# zeta2rework_lw_v22_wo_transistor.net
KiCad netlist of a schematic drawn in EAGLE
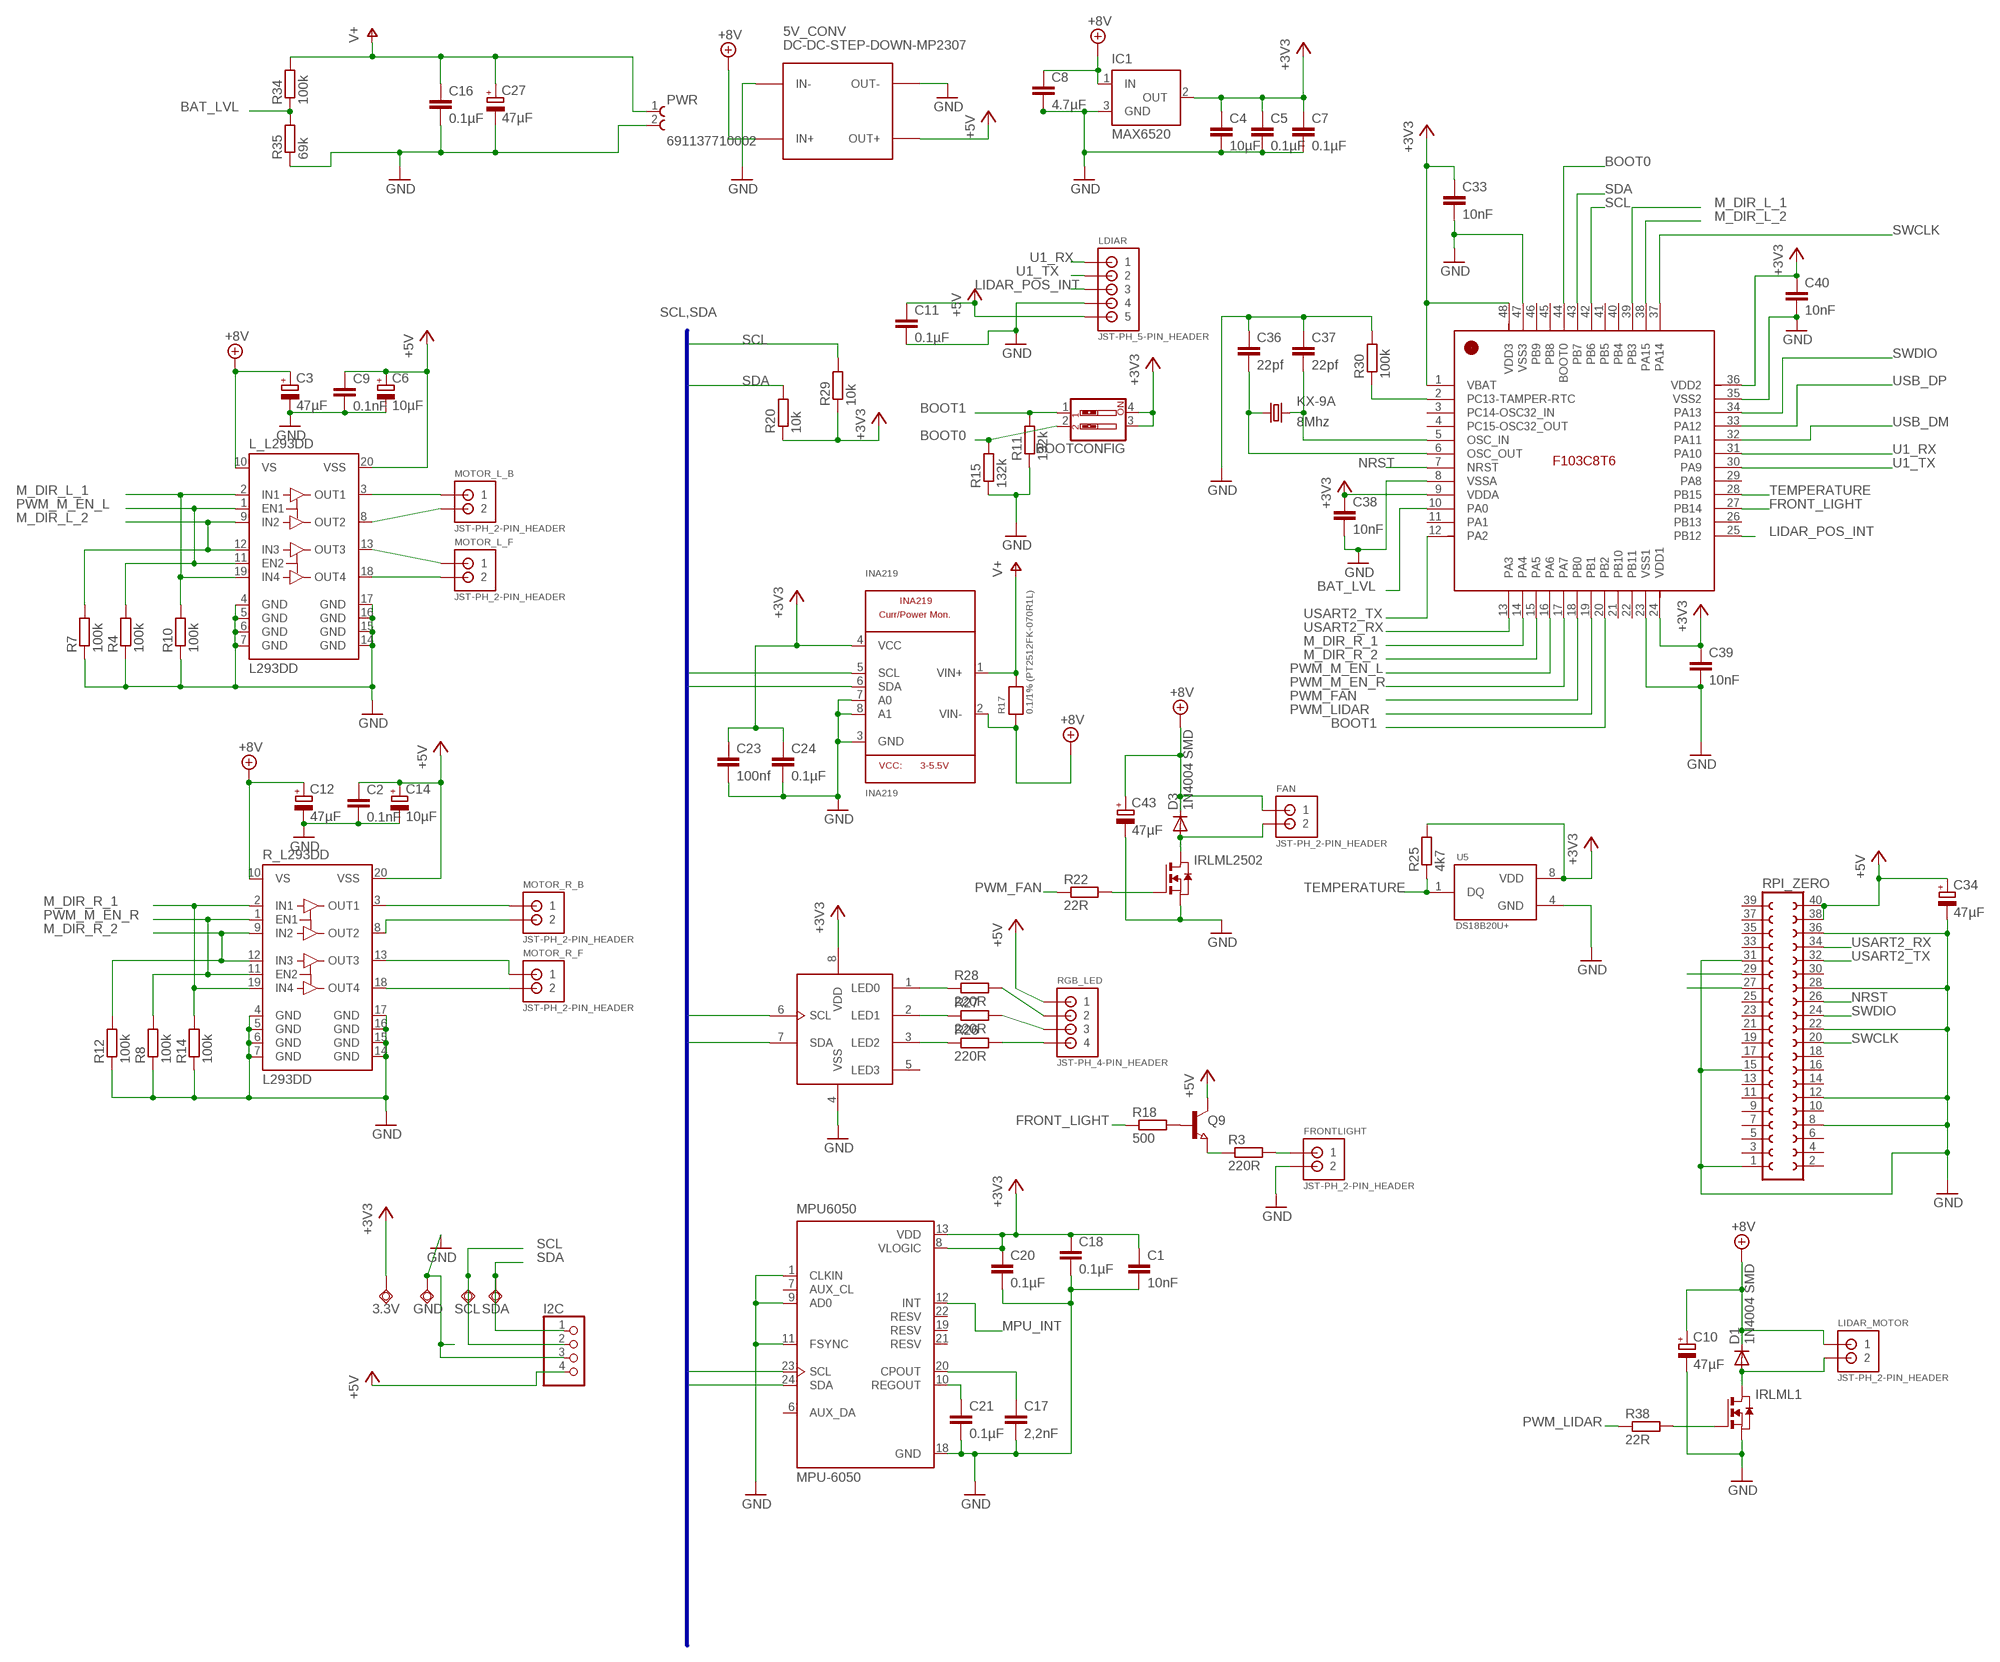
[diagram p0: schematic, sheet 1]

(export (version "E")
  (design (tool "Eeschema 10.0.6"))
  (components
    (comp (ref "3.3V")
      (value "TPSQTP20R")
      (footprint "eagle-import:TP20R")
      (libsource (lib "eagle-import") (part "TPSQTP20R"))
    )
    (comp (ref "5V_CONV")
      (value "DC-DC-STEP-DOWN-MP2307")
      (footprint "eagle-import:DC-DC-STEP-DOWN-MP2307")
      (libsource (lib "eagle-import") (part "DC-DC-STEP-DOWN-MP2307"))
    )
    (comp (ref "BOOTCONFIG")
      (value "SW_DIP-2")
      (footprint "eagle-import:EDG-02")
      (libsource (lib "eagle-import") (part "SW_DIP-2"))
    )
    (comp (ref "C1")
      (value "10nF")
      (footprint "eagle-import:C1206")
      (libsource (lib "eagle-import") (part "C-EUC1206"))
    )
    (comp (ref "C2")
      (value "0.1nF")
      (footprint "eagle-import:C1206")
      (libsource (lib "eagle-import") (part "C-EUC1206"))
    )
    (comp (ref "C3")
      (value "47µF")
      (footprint "eagle-import:UD-4X5,8_NICHICON")
      (libsource (lib "eagle-import") (part "CPOL-EUUD-4X5,8"))
    )
    (comp (ref "C4")
      (value "10µF")
      (footprint "eagle-import:C1206")
      (libsource (lib "eagle-import") (part "C-EUC1206"))
    )
    (comp (ref "C5")
      (value "0.1µF")
      (footprint "eagle-import:C1206")
      (libsource (lib "eagle-import") (part "C-EUC1206"))
    )
    (comp (ref "C6")
      (value "10µF")
      (footprint "eagle-import:UD-4X5,8_NICHICON")
      (libsource (lib "eagle-import") (part "CPOL-EUUD-4X5,8"))
    )
    (comp (ref "C7")
      (value "0.1µF")
      (footprint "eagle-import:C1206")
      (libsource (lib "eagle-import") (part "C-EUC1206"))
    )
    (comp (ref "C8")
      (value "4.7µF")
      (footprint "eagle-import:C1206")
      (libsource (lib "eagle-import") (part "C-EUC1206"))
    )
    (comp (ref "C9")
      (value "0.1nF")
      (footprint "eagle-import:C1206")
      (libsource (lib "eagle-import") (part "C-EUC1206"))
    )
    (comp (ref "C10")
      (value "47µF")
      (footprint "eagle-import:UD-4X5,8_NICHICON")
      (libsource (lib "eagle-import") (part "CPOL-EUUD-4X5,8"))
    )
    (comp (ref "C11")
      (value "0.1µF")
      (footprint "eagle-import:C1206")
      (libsource (lib "eagle-import") (part "C-EUC1206"))
    )
    (comp (ref "C12")
      (value "47µF")
      (footprint "eagle-import:UD-4X5,8_NICHICON")
      (libsource (lib "eagle-import") (part "CPOL-EUUD-4X5,8"))
    )
    (comp (ref "C14")
      (value "10µF")
      (footprint "eagle-import:UD-4X5,8_NICHICON")
      (libsource (lib "eagle-import") (part "CPOL-EUUD-4X5,8"))
    )
    (comp (ref "C16")
      (value "0.1µF")
      (footprint "eagle-import:C1206")
      (libsource (lib "eagle-import") (part "C-EUC1206"))
    )
    (comp (ref "C17")
      (value "2,2nF")
      (footprint "eagle-import:C1206")
      (libsource (lib "eagle-import") (part "C-EUC1206"))
    )
    (comp (ref "C18")
      (value "0.1µF")
      (footprint "eagle-import:C1206")
      (libsource (lib "eagle-import") (part "C-EUC1206"))
    )
    (comp (ref "C20")
      (value "0.1µF")
      (footprint "eagle-import:C1206")
      (libsource (lib "eagle-import") (part "C-EUC1206"))
    )
    (comp (ref "C21")
      (value "0.1µF")
      (footprint "eagle-import:C1206")
      (libsource (lib "eagle-import") (part "C-EUC1206"))
    )
    (comp (ref "C23")
      (value "100nf")
      (footprint "eagle-import:C1206")
      (libsource (lib "eagle-import") (part "C-EUC1206"))
    )
    (comp (ref "C24")
      (value "0.1µF")
      (footprint "eagle-import:C1206")
      (libsource (lib "eagle-import") (part "C-EUC1206"))
    )
    (comp (ref "C27")
      (value "47µF")
      (footprint "eagle-import:UD-4X5,8_NICHICON")
      (libsource (lib "eagle-import") (part "CPOL-EUUD-4X5,8"))
    )
    (comp (ref "C33")
      (value "10nF")
      (footprint "eagle-import:C1206")
      (libsource (lib "eagle-import") (part "C-EUC1206"))
    )
    (comp (ref "C34")
      (value "47µF")
      (footprint "eagle-import:UD-4X5,8_NICHICON")
      (libsource (lib "eagle-import") (part "CPOL-EUUD-4X5,8"))
    )
    (comp (ref "C36")
      (value "22pf")
      (footprint "eagle-import:C1206")
      (libsource (lib "eagle-import") (part "C-EUC1206"))
    )
    (comp (ref "C37")
      (value "22pf")
      (footprint "eagle-import:C1206")
      (libsource (lib "eagle-import") (part "C-EUC1206"))
    )
    (comp (ref "C38")
      (value "10nF")
      (footprint "eagle-import:C1206")
      (libsource (lib "eagle-import") (part "C-EUC1206"))
    )
    (comp (ref "C39")
      (value "10nF")
      (footprint "eagle-import:C1206")
      (libsource (lib "eagle-import") (part "C-EUC1206"))
    )
    (comp (ref "C40")
      (value "10nF")
      (footprint "eagle-import:C1206")
      (libsource (lib "eagle-import") (part "C-EUC1206"))
    )
    (comp (ref "C43")
      (value "47µF")
      (footprint "eagle-import:UD-4X5,8_NICHICON")
      (libsource (lib "eagle-import") (part "CPOL-EUUD-4X5,8"))
    )
    (comp (ref "D1")
      (value "1N4004 SMD")
      (footprint "eagle-import:DO214AC")
      (libsource (lib "eagle-import") (part "DIODE-DO214AC"))
    )
    (comp (ref "D3")
      (value "1N4004 SMD")
      (footprint "eagle-import:DO214AC")
      (libsource (lib "eagle-import") (part "DIODE-DO214AC"))
    )
    (comp (ref "FAN")
      (value "JST-PH_2-PIN_HEADER")
      (footprint "eagle-import:JST_B2B-PH_HEADER")
      (libsource (lib "eagle-import") (part "JST-PH_2-PIN_HEADER"))
    )
    (comp (ref "FRONTLIGHT")
      (value "JST-PH_2-PIN_HEADER")
      (footprint "eagle-import:JST_B2B-PH_HEADER")
      (libsource (lib "eagle-import") (part "JST-PH_2-PIN_HEADER"))
    )
    (comp (ref "GND")
      (value "TPSQTP20R")
      (footprint "eagle-import:TP20R")
      (libsource (lib "eagle-import") (part "TPSQTP20R"))
    )
    (comp (ref "I2C")
      (value "PINHD-1X4")
      (footprint "eagle-import:1X04")
      (libsource (lib "eagle-import") (part "PINHD-1X4"))
    )
    (comp (ref "IC1")
      (value "MAX6520")
      (footprint "eagle-import:SOT23")
      (fields (field (name "MF") "MAXIM") (field (name "MPN") "MAX6520EUR-T"))
      (libsource (lib "eagle-import") (part "MAX6520"))
    )
    (comp (ref "INA219")
      (value "INA219")
      (footprint "eagle-import:SOT23-8")
      (fields (field (name "MF") "Texas Instruments"))
      (libsource (lib "eagle-import") (part "INA219"))
    )
    (comp (ref "IRLML1")
      (value "NMOSSOT23")
      (footprint "eagle-import:SOT-23")
      (libsource (lib "eagle-import") (part "NMOSSOT23"))
    )
    (comp (ref "IRLML2502")
      (value "NMOSSOT23")
      (footprint "eagle-import:SOT-23")
      (libsource (lib "eagle-import") (part "NMOSSOT23"))
    )
    (comp (ref "KX-9A")
      (value "8Mhz")
      (footprint "eagle-import:5.0X3.2_KX-9A")
      (libsource (lib "eagle-import") (part "KX-9A"))
    )
    (comp (ref "LDIAR")
      (value "JST-PH_5-PIN_HEADER")
      (footprint "eagle-import:JST_B5B-PH_HEADER")
      (libsource (lib "eagle-import") (part "JST-PH_5-PIN_HEADER"))
    )
    (comp (ref "LIDAR_MOTOR")
      (value "JST-PH_2-PIN_HEADER")
      (footprint "eagle-import:JST_B2B-PH_HEADER")
      (libsource (lib "eagle-import") (part "JST-PH_2-PIN_HEADER"))
    )
    (comp (ref "L_L293DD")
      (value "L293DD")
      (footprint "eagle-import:SO20")
      (libsource (lib "eagle-import") (part "L293DD"))
    )
    (comp (ref "MOTOR_L_B")
      (value "JST-PH_2-PIN_HEADER")
      (footprint "eagle-import:JST_B2B-PH_HEADER")
      (libsource (lib "eagle-import") (part "JST-PH_2-PIN_HEADER"))
    )
    (comp (ref "MOTOR_L_F")
      (value "JST-PH_2-PIN_HEADER")
      (footprint "eagle-import:JST_B2B-PH_HEADER")
      (libsource (lib "eagle-import") (part "JST-PH_2-PIN_HEADER"))
    )
    (comp (ref "MOTOR_R_B")
      (value "JST-PH_2-PIN_HEADER")
      (footprint "eagle-import:JST_B2B-PH_HEADER")
      (libsource (lib "eagle-import") (part "JST-PH_2-PIN_HEADER"))
    )
    (comp (ref "MOTOR_R_F")
      (value "JST-PH_2-PIN_HEADER")
      (footprint "eagle-import:JST_B2B-PH_HEADER")
      (libsource (lib "eagle-import") (part "JST-PH_2-PIN_HEADER"))
    )
    (comp (ref "MPU6050")
      (value "MPU-6050")
      (footprint "eagle-import:QFN50P400X400X95-24N")
      (fields (field (name "MF") "TDK"))
      (libsource (lib "eagle-import") (part "MPU-6050"))
    )
    (comp (ref "PCA9533")
      (value "PCA9533")
      (footprint "eagle-import:SOIC8")
      (libsource (lib "eagle-import") (part "PCA9533"))
    )
    (comp (ref "PWR")
      (value "691137710002")
      (footprint "eagle-import:691137710002")
      (fields (field (name "MF") "Wurth Electronics"))
      (libsource (lib "eagle-import") (part "691137710002"))
    )
    (comp (ref "Q9")
      (value "NPN-TRANSISTOR_SOT23")
      (footprint "eagle-import:SOT23")
      (libsource (lib "eagle-import") (part "NPN-TRANSISTOR_SOT23"))
    )
    (comp (ref "R3")
      (value "220R")
      (footprint "eagle-import:R0603")
      (libsource (lib "eagle-import") (part "R-EU_R0603"))
    )
    (comp (ref "R4")
      (value "100k")
      (footprint "eagle-import:R0603")
      (libsource (lib "eagle-import") (part "R-EU_R0603"))
    )
    (comp (ref "R7")
      (value "100k")
      (footprint "eagle-import:R0603")
      (libsource (lib "eagle-import") (part "R-EU_R0603"))
    )
    (comp (ref "R8")
      (value "100k")
      (footprint "eagle-import:R0603")
      (libsource (lib "eagle-import") (part "R-EU_R0603"))
    )
    (comp (ref "R10")
      (value "100k")
      (footprint "eagle-import:R0603")
      (libsource (lib "eagle-import") (part "R-EU_R0603"))
    )
    (comp (ref "R11")
      (value "132k")
      (footprint "eagle-import:R0603")
      (libsource (lib "eagle-import") (part "R-EU_R0603"))
    )
    (comp (ref "R12")
      (value "100k")
      (footprint "eagle-import:R0603")
      (libsource (lib "eagle-import") (part "R-EU_R0603"))
    )
    (comp (ref "R14")
      (value "100k")
      (footprint "eagle-import:R0603")
      (libsource (lib "eagle-import") (part "R-EU_R0603"))
    )
    (comp (ref "R15")
      (value "132k")
      (footprint "eagle-import:R0603")
      (libsource (lib "eagle-import") (part "R-EU_R0603"))
    )
    (comp (ref "R17")
      (value "0.1/1% (PT2512FK-070R1L)")
      (footprint "eagle-import:2512")
      (libsource (lib "eagle-import") (part "RESISTOR2512"))
    )
    (comp (ref "R18")
      (value "500")
      (footprint "eagle-import:R0603")
      (libsource (lib "eagle-import") (part "R-EU_R0603"))
    )
    (comp (ref "R20")
      (value "10k")
      (footprint "eagle-import:R0603")
      (libsource (lib "eagle-import") (part "R-EU_R0603"))
    )
    (comp (ref "R22")
      (value "22R")
      (footprint "eagle-import:R0603")
      (libsource (lib "eagle-import") (part "R-EU_R0603"))
    )
    (comp (ref "R25")
      (value "4k7")
      (footprint "eagle-import:R0603")
      (libsource (lib "eagle-import") (part "R-EU_R0603"))
    )
    (comp (ref "R26")
      (value "220R")
      (footprint "eagle-import:R0603")
      (libsource (lib "eagle-import") (part "R-EU_R0603"))
    )
    (comp (ref "R27")
      (value "220R")
      (footprint "eagle-import:R0603")
      (libsource (lib "eagle-import") (part "R-EU_R0603"))
    )
    (comp (ref "R28")
      (value "220R")
      (footprint "eagle-import:R0603")
      (libsource (lib "eagle-import") (part "R-EU_R0603"))
    )
    (comp (ref "R29")
      (value "10k")
      (footprint "eagle-import:R0603")
      (libsource (lib "eagle-import") (part "R-EU_R0603"))
    )
    (comp (ref "R30")
      (value "100k")
      (footprint "eagle-import:R0603")
      (libsource (lib "eagle-import") (part "R-EU_R0603"))
    )
    (comp (ref "R34")
      (value "100k")
      (footprint "eagle-import:R0603")
      (libsource (lib "eagle-import") (part "R-EU_R0603"))
    )
    (comp (ref "R35")
      (value "69k")
      (footprint "eagle-import:R0603")
      (libsource (lib "eagle-import") (part "R-EU_R0603"))
    )
    (comp (ref "R38")
      (value "22R")
      (footprint "eagle-import:R0603")
      (libsource (lib "eagle-import") (part "R-EU_R0603"))
    )
    (comp (ref "RGB_LED")
      (value "JST-PH_4-PIN_HEADER")
      (footprint "eagle-import:JST_B4B-PH_HEADER")
      (libsource (lib "eagle-import") (part "JST-PH_4-PIN_HEADER"))
    )
    (comp (ref "RPI_ZERO")
      (value "FE20-2")
      (footprint "eagle-import:FE20-2")
      (libsource (lib "eagle-import") (part "FE20-2"))
    )
    (comp (ref "R_L293DD")
      (value "L293DD")
      (footprint "eagle-import:SO20")
      (libsource (lib "eagle-import") (part "L293DD"))
    )
    (comp (ref "SCL")
      (value "TPSQTP20R")
      (footprint "eagle-import:TP20R")
      (libsource (lib "eagle-import") (part "TPSQTP20R"))
    )
    (comp (ref "SDA")
      (value "TPSQTP20R")
      (footprint "eagle-import:TP20R")
      (libsource (lib "eagle-import") (part "TPSQTP20R"))
    )
    (comp (ref "STM32F103CB")
      (value "STM32F103CB")
      (footprint "eagle-import:LQFP48_7X7MM_0.5MMPP")
      (fields (field (name "MF") "STMicroelectronics") (field (name "MP") "STM32F103C8T6"))
      (libsource (lib "eagle-import") (part "STM32F103C8T6"))
    )
    (comp (ref "U5")
      (value "DS18B20U+")
      (footprint "eagle-import:SOP65P490X95-8N")
      (fields (field (name "MF") "Maxim"))
      (libsource (lib "eagle-import") (part "DS18B20U+"))
    )
  )
  (nets
    (net (code "1") (name "+3V3") (class "Default")
      (node (ref "3.3V") (pin "TP") (pinfunction "TP_TP") (pintype "input"))
      (node (ref "BOOTCONFIG") (pin "3") (pinfunction "3_3") (pintype "passive"))
      (node (ref "BOOTCONFIG") (pin "4") (pinfunction "4_4") (pintype "passive"))
      (node (ref "C1") (pin "1") (pinfunction "1_1") (pintype "passive"))
      (node (ref "C18") (pin "1") (pinfunction "1_1") (pintype "passive"))
      (node (ref "C20") (pin "1") (pinfunction "1_1") (pintype "passive"))
      (node (ref "C23") (pin "1") (pinfunction "1_1") (pintype "passive"))
      (node (ref "C24") (pin "1") (pinfunction "1_1") (pintype "passive"))
      (node (ref "C33") (pin "1") (pinfunction "1_1") (pintype "passive"))
      (node (ref "C38") (pin "1") (pinfunction "1_1") (pintype "passive"))
      (node (ref "C39") (pin "1") (pinfunction "1_1") (pintype "passive"))
      (node (ref "C4") (pin "1") (pinfunction "1_1") (pintype "passive"))
      (node (ref "C40") (pin "1") (pinfunction "1_1") (pintype "passive"))
      (node (ref "C5") (pin "1") (pinfunction "1_1") (pintype "passive"))
      (node (ref "C7") (pin "1") (pinfunction "1_1") (pintype "passive"))
      (node (ref "IC1") (pin "2") (pinfunction "OUT_2") (pintype "output"))
      (node (ref "INA219") (pin "4") (pinfunction "VCC_4") (pintype "bidirectional"))
      (node (ref "MPU6050") (pin "13") (pinfunction "VDD_13") (pintype "power_in"))
      (node (ref "MPU6050") (pin "8") (pinfunction "VLOGIC_8") (pintype "power_in"))
      (node (ref "PCA9533") (pin "8") (pinfunction "VDD_8") (pintype "power_in"))
      (node (ref "R20") (pin "1") (pinfunction "1_1") (pintype "passive"))
      (node (ref "R25") (pin "2") (pinfunction "2_2") (pintype "passive"))
      (node (ref "R29") (pin "1") (pinfunction "1_1") (pintype "passive"))
      (node (ref "STM32F103CB") (pin "1") (pinfunction "VBAT_1") (pintype "bidirectional"))
      (node (ref "STM32F103CB") (pin "24") (pinfunction "VDD1_24") (pintype "bidirectional"))
      (node (ref "STM32F103CB") (pin "36") (pinfunction "VDD2_36") (pintype "bidirectional"))
      (node (ref "STM32F103CB") (pin "48") (pinfunction "VDD3_48") (pintype "bidirectional"))
      (node (ref "STM32F103CB") (pin "9") (pinfunction "VDDA_9") (pintype "bidirectional"))
      (node (ref "U5") (pin "8") (pinfunction "VDD_8") (pintype "power_in"))
    )
    (net (code "2") (name "+5V") (class "Default")
      (node (ref "5V_CONV") (pin "OUT+") (pinfunction "OUT+_OUT+") (pintype "bidirectional"))
      (node (ref "C11") (pin "1") (pinfunction "1_1") (pintype "passive"))
      (node (ref "C14") (pin "+") (pinfunction "+_+") (pintype "passive"))
      (node (ref "C2") (pin "1") (pinfunction "1_1") (pintype "passive"))
      (node (ref "C34") (pin "+") (pinfunction "+_+") (pintype "passive"))
      (node (ref "C6") (pin "+") (pinfunction "+_+") (pintype "passive"))
      (node (ref "C9") (pin "1") (pinfunction "1_1") (pintype "passive"))
      (node (ref "I2C") (pin "4") (pinfunction "4_4") (pintype "passive"))
      (node (ref "LDIAR") (pin "P5") (pinfunction "5_P5") (pintype "bidirectional"))
      (node (ref "L_L293DD") (pin "20") (pinfunction "VSS_20") (pintype "power_in"))
      (node (ref "Q9") (pin "3") (pinfunction "C_3") (pintype "passive"))
      (node (ref "RGB_LED") (pin "P1") (pinfunction "1_P1") (pintype "bidirectional"))
      (node (ref "RPI_ZERO") (pin "38") (pinfunction "38_38") (pintype "passive"))
      (node (ref "RPI_ZERO") (pin "40") (pinfunction "40_40") (pintype "passive"))
      (node (ref "R_L293DD") (pin "20") (pinfunction "VSS_20") (pintype "power_in"))
    )
    (net (code "3") (name "+8V") (class "Default")
      (node (ref "5V_CONV") (pin "IN+") (pinfunction "IN+_IN+") (pintype "bidirectional"))
      (node (ref "C10") (pin "+") (pinfunction "+_+") (pintype "passive"))
      (node (ref "C12") (pin "+") (pinfunction "+_+") (pintype "passive"))
      (node (ref "C3") (pin "+") (pinfunction "+_+") (pintype "passive"))
      (node (ref "C43") (pin "+") (pinfunction "+_+") (pintype "passive"))
      (node (ref "C8") (pin "1") (pinfunction "1_1") (pintype "passive"))
      (node (ref "D1") (pin "C") (pinfunction "C_C") (pintype "passive"))
      (node (ref "D3") (pin "C") (pinfunction "C_C") (pintype "passive"))
      (node (ref "FAN") (pin "P1") (pinfunction "1_P1") (pintype "bidirectional"))
      (node (ref "IC1") (pin "1") (pinfunction "IN_1") (pintype "input"))
      (node (ref "INA219") (pin "2") (pinfunction "VIN-_2") (pintype "bidirectional"))
      (node (ref "LIDAR_MOTOR") (pin "P1") (pinfunction "1_P1") (pintype "bidirectional"))
      (node (ref "L_L293DD") (pin "10") (pinfunction "VS_10") (pintype "power_in"))
      (node (ref "R17") (pin "1") (pinfunction "1_1") (pintype "passive"))
      (node (ref "R_L293DD") (pin "10") (pinfunction "VS_10") (pintype "power_in"))
    )
    (net (code "4") (name "/BAT_LVL") (class "Default")
      (node (ref "R34") (pin "1") (pinfunction "1_1") (pintype "passive"))
      (node (ref "R35") (pin "2") (pinfunction "2_2") (pintype "passive"))
      (node (ref "STM32F103CB") (pin "10") (pinfunction "PA0_10") (pintype "bidirectional"))
    )
    (net (code "5") (name "/BOOT0") (class "Default")
      (node (ref "BOOTCONFIG") (pin "2") (pinfunction "2_2") (pintype "passive"))
      (node (ref "R15") (pin "2") (pinfunction "2_2") (pintype "passive"))
      (node (ref "STM32F103CB") (pin "44") (pinfunction "BOOT0_44") (pintype "bidirectional"))
    )
    (net (code "6") (name "/BOOT1") (class "Default")
      (node (ref "BOOTCONFIG") (pin "1") (pinfunction "1_1") (pintype "passive"))
      (node (ref "R11") (pin "2") (pinfunction "2_2") (pintype "passive"))
      (node (ref "STM32F103CB") (pin "20") (pinfunction "PB2_20") (pintype "bidirectional"))
    )
    (net (code "7") (name "/FRONT_LIGHT") (class "Default")
      (node (ref "R18") (pin "1") (pinfunction "1_1") (pintype "passive"))
      (node (ref "STM32F103CB") (pin "27") (pinfunction "PB14_27") (pintype "bidirectional"))
    )
    (net (code "8") (name "/LIDAR_POS_INT") (class "Default")
      (node (ref "LDIAR") (pin "P3") (pinfunction "3_P3") (pintype "bidirectional"))
      (node (ref "STM32F103CB") (pin "25") (pinfunction "PB12_25") (pintype "bidirectional"))
    )
    (net (code "9") (name "/MPU_INT") (class "Default")
      (node (ref "MPU6050") (pin "12") (pinfunction "INT_12") (pintype "output"))
    )
    (net (code "10") (name "/M_DIR_L_1") (class "Default")
      (node (ref "L_L293DD") (pin "19") (pinfunction "IN4_19") (pintype "input"))
      (node (ref "L_L293DD") (pin "2") (pinfunction "IN1_2") (pintype "input"))
      (node (ref "R10") (pin "2") (pinfunction "2_2") (pintype "passive"))
      (node (ref "STM32F103CB") (pin "39") (pinfunction "PB3_39") (pintype "bidirectional"))
    )
    (net (code "11") (name "/M_DIR_L_2") (class "Default")
      (node (ref "L_L293DD") (pin "12") (pinfunction "IN3_12") (pintype "input"))
      (node (ref "L_L293DD") (pin "9") (pinfunction "IN2_9") (pintype "input"))
      (node (ref "R7") (pin "2") (pinfunction "2_2") (pintype "passive"))
      (node (ref "STM32F103CB") (pin "38") (pinfunction "PA15_38") (pintype "bidirectional"))
    )
    (net (code "12") (name "/M_DIR_R_1") (class "Default")
      (node (ref "R14") (pin "2") (pinfunction "2_2") (pintype "passive"))
      (node (ref "R_L293DD") (pin "19") (pinfunction "IN4_19") (pintype "input"))
      (node (ref "R_L293DD") (pin "2") (pinfunction "IN1_2") (pintype "input"))
      (node (ref "STM32F103CB") (pin "14") (pinfunction "PA4_14") (pintype "bidirectional"))
    )
    (net (code "13") (name "/M_DIR_R_2") (class "Default")
      (node (ref "R12") (pin "2") (pinfunction "2_2") (pintype "passive"))
      (node (ref "R_L293DD") (pin "12") (pinfunction "IN3_12") (pintype "input"))
      (node (ref "R_L293DD") (pin "9") (pinfunction "IN2_9") (pintype "input"))
      (node (ref "STM32F103CB") (pin "15") (pinfunction "PA5_15") (pintype "bidirectional"))
    )
    (net (code "14") (name "/NRST") (class "Default")
      (node (ref "RPI_ZERO") (pin "26") (pinfunction "26_26") (pintype "passive"))
      (node (ref "STM32F103CB") (pin "7") (pinfunction "NRST_7") (pintype "bidirectional"))
    )
    (net (code "15") (name "/PWM_FAN") (class "Default")
      (node (ref "R22") (pin "1") (pinfunction "1_1") (pintype "passive"))
      (node (ref "STM32F103CB") (pin "18") (pinfunction "PB0_18") (pintype "bidirectional"))
    )
    (net (code "16") (name "/PWM_LIDAR") (class "Default")
      (node (ref "R38") (pin "1") (pinfunction "1_1") (pintype "passive"))
      (node (ref "STM32F103CB") (pin "19") (pinfunction "PB1_19") (pintype "bidirectional"))
    )
    (net (code "17") (name "/PWM_M_EN_L") (class "Default")
      (node (ref "L_L293DD") (pin "1") (pinfunction "EN1_1") (pintype "input"))
      (node (ref "L_L293DD") (pin "11") (pinfunction "EN2_11") (pintype "input"))
      (node (ref "R4") (pin "2") (pinfunction "2_2") (pintype "passive"))
      (node (ref "STM32F103CB") (pin "16") (pinfunction "PA6_16") (pintype "bidirectional"))
    )
    (net (code "18") (name "/PWM_M_EN_R") (class "Default")
      (node (ref "R8") (pin "2") (pinfunction "2_2") (pintype "passive"))
      (node (ref "R_L293DD") (pin "1") (pinfunction "EN1_1") (pintype "input"))
      (node (ref "R_L293DD") (pin "11") (pinfunction "EN2_11") (pintype "input"))
      (node (ref "STM32F103CB") (pin "17") (pinfunction "PA7_17") (pintype "bidirectional"))
    )
    (net (code "19") (name "/SCL") (class "Default")
      (node (ref "I2C") (pin "2") (pinfunction "2_2") (pintype "passive"))
      (node (ref "INA219") (pin "5") (pinfunction "SCL_5") (pintype "bidirectional"))
      (node (ref "MPU6050") (pin "23") (pinfunction "SCL_23") (pintype "input"))
      (node (ref "PCA9533") (pin "6") (pinfunction "SCL_6") (pintype "input"))
      (node (ref "R29") (pin "2") (pinfunction "2_2") (pintype "passive"))
      (node (ref "SCL") (pin "TP") (pinfunction "TP_TP") (pintype "input"))
      (node (ref "STM32F103CB") (pin "42") (pinfunction "PB6_42") (pintype "bidirectional"))
    )
    (net (code "20") (name "/SDA") (class "Default")
      (node (ref "I2C") (pin "1") (pinfunction "1_1") (pintype "passive"))
      (node (ref "INA219") (pin "6") (pinfunction "SDA_6") (pintype "bidirectional"))
      (node (ref "MPU6050") (pin "24") (pinfunction "SDA_24") (pintype "bidirectional"))
      (node (ref "PCA9533") (pin "7") (pinfunction "SDA_7") (pintype "bidirectional"))
      (node (ref "R20") (pin "2") (pinfunction "2_2") (pintype "passive"))
      (node (ref "SDA") (pin "TP") (pinfunction "TP_TP") (pintype "input"))
      (node (ref "STM32F103CB") (pin "43") (pinfunction "PB7_43") (pintype "bidirectional"))
    )
    (net (code "21") (name "/SWCLK") (class "Default")
      (node (ref "RPI_ZERO") (pin "20") (pinfunction "20_20") (pintype "passive"))
      (node (ref "STM32F103CB") (pin "37") (pinfunction "PA14_37") (pintype "bidirectional"))
    )
    (net (code "22") (name "/SWDIO") (class "Default")
      (node (ref "RPI_ZERO") (pin "24") (pinfunction "24_24") (pintype "passive"))
      (node (ref "STM32F103CB") (pin "34") (pinfunction "PA13_34") (pintype "bidirectional"))
    )
    (net (code "23") (name "/TEMPERATURE") (class "Default")
      (node (ref "R25") (pin "1") (pinfunction "1_1") (pintype "passive"))
      (node (ref "STM32F103CB") (pin "28") (pinfunction "PB15_28") (pintype "bidirectional"))
      (node (ref "U5") (pin "1") (pinfunction "DQ_1") (pintype "bidirectional"))
    )
    (net (code "24") (name "/U1_RX") (class "Default")
      (node (ref "LDIAR") (pin "P1") (pinfunction "1_P1") (pintype "bidirectional"))
      (node (ref "STM32F103CB") (pin "31") (pinfunction "PA10_31") (pintype "bidirectional"))
    )
    (net (code "25") (name "/U1_TX") (class "Default")
      (node (ref "LDIAR") (pin "P2") (pinfunction "2_P2") (pintype "bidirectional"))
      (node (ref "STM32F103CB") (pin "30") (pinfunction "PA9_30") (pintype "bidirectional"))
    )
    (net (code "26") (name "/USART2_RX") (class "Default")
      (node (ref "RPI_ZERO") (pin "34") (pinfunction "34_34") (pintype "passive"))
      (node (ref "STM32F103CB") (pin "13") (pinfunction "PA3_13") (pintype "bidirectional"))
    )
    (net (code "27") (name "/USART2_TX") (class "Default")
      (node (ref "RPI_ZERO") (pin "32") (pinfunction "32_32") (pintype "passive"))
      (node (ref "STM32F103CB") (pin "12") (pinfunction "PA2_12") (pintype "bidirectional"))
    )
    (net (code "28") (name "/USB_DM") (class "Default")
      (node (ref "STM32F103CB") (pin "32") (pinfunction "PA11_32") (pintype "bidirectional"))
    )
    (net (code "29") (name "/USB_DP") (class "Default")
      (node (ref "STM32F103CB") (pin "33") (pinfunction "PA12_33") (pintype "bidirectional"))
    )
    (net (code "31") (name "GND") (class "Default")
      (node (ref "5V_CONV") (pin "IN-") (pinfunction "IN-_IN-") (pintype "bidirectional"))
      (node (ref "5V_CONV") (pin "OUT-") (pinfunction "OUT-_OUT-") (pintype "bidirectional"))
      (node (ref "C1") (pin "2") (pinfunction "2_2") (pintype "passive"))
      (node (ref "C10") (pin "-") (pinfunction "-_-") (pintype "passive"))
      (node (ref "C11") (pin "2") (pinfunction "2_2") (pintype "passive"))
      (node (ref "C12") (pin "-") (pinfunction "-_-") (pintype "passive"))
      (node (ref "C14") (pin "-") (pinfunction "-_-") (pintype "passive"))
      (node (ref "C16") (pin "2") (pinfunction "2_2") (pintype "passive"))
      (node (ref "C17") (pin "2") (pinfunction "2_2") (pintype "passive"))
      (node (ref "C18") (pin "2") (pinfunction "2_2") (pintype "passive"))
      (node (ref "C2") (pin "2") (pinfunction "2_2") (pintype "passive"))
      (node (ref "C20") (pin "2") (pinfunction "2_2") (pintype "passive"))
      (node (ref "C21") (pin "2") (pinfunction "2_2") (pintype "passive"))
      (node (ref "C23") (pin "2") (pinfunction "2_2") (pintype "passive"))
      (node (ref "C24") (pin "2") (pinfunction "2_2") (pintype "passive"))
      (node (ref "C27") (pin "-") (pinfunction "-_-") (pintype "passive"))
      (node (ref "C3") (pin "-") (pinfunction "-_-") (pintype "passive"))
      (node (ref "C33") (pin "2") (pinfunction "2_2") (pintype "passive"))
      (node (ref "C34") (pin "-") (pinfunction "-_-") (pintype "passive"))
      (node (ref "C36") (pin "1") (pinfunction "1_1") (pintype "passive"))
      (node (ref "C37") (pin "1") (pinfunction "1_1") (pintype "passive"))
      (node (ref "C38") (pin "2") (pinfunction "2_2") (pintype "passive"))
      (node (ref "C39") (pin "2") (pinfunction "2_2") (pintype "passive"))
      (node (ref "C4") (pin "2") (pinfunction "2_2") (pintype "passive"))
      (node (ref "C40") (pin "2") (pinfunction "2_2") (pintype "passive"))
      (node (ref "C43") (pin "-") (pinfunction "-_-") (pintype "passive"))
      (node (ref "C5") (pin "2") (pinfunction "2_2") (pintype "passive"))
      (node (ref "C6") (pin "-") (pinfunction "-_-") (pintype "passive"))
      (node (ref "C7") (pin "2") (pinfunction "2_2") (pintype "passive"))
      (node (ref "C8") (pin "2") (pinfunction "2_2") (pintype "passive"))
      (node (ref "C9") (pin "2") (pinfunction "2_2") (pintype "passive"))
      (node (ref "FRONTLIGHT") (pin "P2") (pinfunction "2_P2") (pintype "bidirectional"))
      (node (ref "GND") (pin "TP") (pinfunction "TP_TP") (pintype "input"))
      (node (ref "I2C") (pin "3") (pinfunction "3_3") (pintype "passive"))
      (node (ref "IC1") (pin "3") (pinfunction "GND_3") (pintype "power_in"))
      (node (ref "INA219") (pin "3") (pinfunction "GND_3") (pintype "bidirectional"))
      (node (ref "INA219") (pin "7") (pinfunction "A0_7") (pintype "bidirectional"))
      (node (ref "INA219") (pin "8") (pinfunction "A1_8") (pintype "bidirectional"))
      (node (ref "IRLML1") (pin "2") (pinfunction "S_2") (pintype "passive"))
      (node (ref "IRLML2502") (pin "2") (pinfunction "S_2") (pintype "passive"))
      (node (ref "LDIAR") (pin "P4") (pinfunction "4_P4") (pintype "bidirectional"))
      (node (ref "L_L293DD") (pin "14") (pinfunction "GND_14") (pintype "power_in"))
      (node (ref "L_L293DD") (pin "15") (pinfunction "GND_15") (pintype "power_in"))
      (node (ref "L_L293DD") (pin "16") (pinfunction "GND_16") (pintype "power_in"))
      (node (ref "L_L293DD") (pin "17") (pinfunction "GND_17") (pintype "power_in"))
      (node (ref "L_L293DD") (pin "4") (pinfunction "GND_4") (pintype "power_in"))
      (node (ref "L_L293DD") (pin "5") (pinfunction "GND_5") (pintype "power_in"))
      (node (ref "L_L293DD") (pin "6") (pinfunction "GND_6") (pintype "power_in"))
      (node (ref "L_L293DD") (pin "7") (pinfunction "GND_7") (pintype "power_in"))
      (node (ref "MPU6050") (pin "1") (pinfunction "CLKIN_1") (pintype "input"))
      (node (ref "MPU6050") (pin "11") (pinfunction "FSYNC_11") (pintype "input"))
      (node (ref "MPU6050") (pin "18") (pinfunction "GND_18") (pintype "power_in"))
      (node (ref "MPU6050") (pin "9") (pinfunction "AD0_9") (pintype "input"))
      (node (ref "PCA9533") (pin "4") (pinfunction "VSS_4") (pintype "power_in"))
      (node (ref "PWR") (pin "2") (pinfunction "2_2") (pintype "passive"))
      (node (ref "R10") (pin "1") (pinfunction "1_1") (pintype "passive"))
      (node (ref "R11") (pin "1") (pinfunction "1_1") (pintype "passive"))
      (node (ref "R12") (pin "1") (pinfunction "1_1") (pintype "passive"))
      (node (ref "R14") (pin "1") (pinfunction "1_1") (pintype "passive"))
      (node (ref "R15") (pin "1") (pinfunction "1_1") (pintype "passive"))
      (node (ref "R30") (pin "2") (pinfunction "2_2") (pintype "passive"))
      (node (ref "R35") (pin "1") (pinfunction "1_1") (pintype "passive"))
      (node (ref "R4") (pin "1") (pinfunction "1_1") (pintype "passive"))
      (node (ref "R7") (pin "1") (pinfunction "1_1") (pintype "passive"))
      (node (ref "R8") (pin "1") (pinfunction "1_1") (pintype "passive"))
      (node (ref "RPI_ZERO") (pin "1") (pinfunction "1_1") (pintype "passive"))
      (node (ref "RPI_ZERO") (pin "12") (pinfunction "12_12") (pintype "passive"))
      (node (ref "RPI_ZERO") (pin "15") (pinfunction "15_15") (pintype "passive"))
      (node (ref "RPI_ZERO") (pin "22") (pinfunction "22_22") (pintype "passive"))
      (node (ref "RPI_ZERO") (pin "28") (pinfunction "28_28") (pintype "passive"))
      (node (ref "RPI_ZERO") (pin "31") (pinfunction "31_31") (pintype "passive"))
      (node (ref "RPI_ZERO") (pin "36") (pinfunction "36_36") (pintype "passive"))
      (node (ref "RPI_ZERO") (pin "8") (pinfunction "8_8") (pintype "passive"))
      (node (ref "R_L293DD") (pin "14") (pinfunction "GND_14") (pintype "power_in"))
      (node (ref "R_L293DD") (pin "15") (pinfunction "GND_15") (pintype "power_in"))
      (node (ref "R_L293DD") (pin "16") (pinfunction "GND_16") (pintype "power_in"))
      (node (ref "R_L293DD") (pin "17") (pinfunction "GND_17") (pintype "power_in"))
      (node (ref "R_L293DD") (pin "4") (pinfunction "GND_4") (pintype "power_in"))
      (node (ref "R_L293DD") (pin "5") (pinfunction "GND_5") (pintype "power_in"))
      (node (ref "R_L293DD") (pin "6") (pinfunction "GND_6") (pintype "power_in"))
      (node (ref "R_L293DD") (pin "7") (pinfunction "GND_7") (pintype "power_in"))
      (node (ref "STM32F103CB") (pin "23") (pinfunction "VSS1_23") (pintype "bidirectional"))
      (node (ref "STM32F103CB") (pin "35") (pinfunction "VSS2_35") (pintype "bidirectional"))
      (node (ref "STM32F103CB") (pin "47") (pinfunction "VSS3_47") (pintype "bidirectional"))
      (node (ref "STM32F103CB") (pin "8") (pinfunction "VSSA_8") (pintype "bidirectional"))
      (node (ref "U5") (pin "4") (pinfunction "GND_4") (pintype "power_in"))
    )
    (net (code "32") (name "Net-(FAN-2)") (class "Default")
      (node (ref "D3") (pin "A") (pinfunction "A_A") (pintype "passive"))
      (node (ref "FAN") (pin "P2") (pinfunction "2_P2") (pintype "bidirectional"))
      (node (ref "IRLML2502") (pin "1") (pinfunction "D_1") (pintype "passive"))
    )
    (net (code "33") (name "Net-(FRONTLIGHT-1)") (class "Default")
      (node (ref "FRONTLIGHT") (pin "P1") (pinfunction "1_P1") (pintype "bidirectional"))
      (node (ref "R3") (pin "2") (pinfunction "2_2") (pintype "passive"))
    )
    (net (code "34") (name "Net-(IRLML1-D)") (class "Default")
      (node (ref "D1") (pin "A") (pinfunction "A_A") (pintype "passive"))
      (node (ref "IRLML1") (pin "1") (pinfunction "D_1") (pintype "passive"))
      (node (ref "LIDAR_MOTOR") (pin "P2") (pinfunction "2_P2") (pintype "bidirectional"))
    )
    (net (code "35") (name "Net-(IRLML1-G)") (class "Default")
      (node (ref "IRLML1") (pin "3") (pinfunction "G_3") (pintype "passive"))
      (node (ref "R38") (pin "2") (pinfunction "2_2") (pintype "passive"))
    )
    (net (code "36") (name "Net-(IRLML2502-G)") (class "Default")
      (node (ref "IRLML2502") (pin "3") (pinfunction "G_3") (pintype "passive"))
      (node (ref "R22") (pin "2") (pinfunction "2_2") (pintype "passive"))
    )
    (net (code "37") (name "Net-(KX-9A-2)") (class "Default")
      (node (ref "C37") (pin "2") (pinfunction "2_2") (pintype "passive"))
      (node (ref "KX-9A") (pin "3") (pinfunction "2_3") (pintype "passive"))
      (node (ref "STM32F103CB") (pin "5") (pinfunction "OSC_IN_5") (pintype "bidirectional"))
    )
    (net (code "38") (name "Net-(L_L293DD-OUT1)") (class "Default")
      (node (ref "L_L293DD") (pin "3") (pinfunction "OUT1_3") (pintype "output"))
      (node (ref "MOTOR_L_B") (pin "P1") (pinfunction "1_P1") (pintype "bidirectional"))
    )
    (net (code "39") (name "Net-(L_L293DD-OUT2)") (class "Default")
      (node (ref "L_L293DD") (pin "8") (pinfunction "OUT2_8") (pintype "output"))
      (node (ref "MOTOR_L_B") (pin "P2") (pinfunction "2_P2") (pintype "bidirectional"))
    )
    (net (code "40") (name "Net-(L_L293DD-OUT3)") (class "Default")
      (node (ref "L_L293DD") (pin "13") (pinfunction "OUT3_13") (pintype "output"))
      (node (ref "MOTOR_L_F") (pin "P1") (pinfunction "1_P1") (pintype "bidirectional"))
    )
    (net (code "41") (name "Net-(L_L293DD-OUT4)") (class "Default")
      (node (ref "L_L293DD") (pin "18") (pinfunction "OUT4_18") (pintype "output"))
      (node (ref "MOTOR_L_F") (pin "P2") (pinfunction "2_P2") (pintype "bidirectional"))
    )
    (net (code "42") (name "Net-(MOTOR_R_B-1)") (class "Default")
      (node (ref "MOTOR_R_B") (pin "P1") (pinfunction "1_P1") (pintype "bidirectional"))
      (node (ref "R_L293DD") (pin "3") (pinfunction "OUT1_3") (pintype "output"))
    )
    (net (code "43") (name "Net-(MOTOR_R_B-2)") (class "Default")
      (node (ref "MOTOR_R_B") (pin "P2") (pinfunction "2_P2") (pintype "bidirectional"))
      (node (ref "R_L293DD") (pin "8") (pinfunction "OUT2_8") (pintype "output"))
    )
    (net (code "44") (name "Net-(MOTOR_R_F-1)") (class "Default")
      (node (ref "MOTOR_R_F") (pin "P1") (pinfunction "1_P1") (pintype "bidirectional"))
      (node (ref "R_L293DD") (pin "13") (pinfunction "OUT3_13") (pintype "output"))
    )
    (net (code "45") (name "Net-(MOTOR_R_F-2)") (class "Default")
      (node (ref "MOTOR_R_F") (pin "P2") (pinfunction "2_P2") (pintype "bidirectional"))
      (node (ref "R_L293DD") (pin "18") (pinfunction "OUT4_18") (pintype "output"))
    )
    (net (code "46") (name "Net-(MPU6050-CPOUT)") (class "Default")
      (node (ref "C17") (pin "1") (pinfunction "1_1") (pintype "passive"))
      (node (ref "MPU6050") (pin "20") (pinfunction "CPOUT_20") (pintype "passive"))
    )
    (net (code "47") (name "Net-(MPU6050-REGOUT)") (class "Default")
      (node (ref "C21") (pin "1") (pinfunction "1_1") (pintype "passive"))
      (node (ref "MPU6050") (pin "10") (pinfunction "REGOUT_10") (pintype "passive"))
    )
    (net (code "48") (name "Net-(PCA9533-LED0)") (class "Default")
      (node (ref "PCA9533") (pin "1") (pinfunction "LED0_1") (pintype "bidirectional"))
      (node (ref "R28") (pin "1") (pinfunction "1_1") (pintype "passive"))
    )
    (net (code "49") (name "Net-(PCA9533-LED1)") (class "Default")
      (node (ref "PCA9533") (pin "2") (pinfunction "LED1_2") (pintype "bidirectional"))
      (node (ref "R27") (pin "1") (pinfunction "1_1") (pintype "passive"))
    )
    (net (code "50") (name "Net-(PCA9533-LED2)") (class "Default")
      (node (ref "PCA9533") (pin "3") (pinfunction "LED2_3") (pintype "bidirectional"))
      (node (ref "R26") (pin "1") (pinfunction "1_1") (pintype "passive"))
    )
    (net (code "51") (name "Net-(Q9-B)") (class "Default")
      (node (ref "Q9") (pin "1") (pinfunction "B_1") (pintype "passive"))
      (node (ref "R18") (pin "2") (pinfunction "2_2") (pintype "passive"))
    )
    (net (code "52") (name "Net-(Q9-E)") (class "Default")
      (node (ref "Q9") (pin "2") (pinfunction "E_2") (pintype "passive"))
      (node (ref "R3") (pin "1") (pinfunction "1_1") (pintype "passive"))
    )
    (net (code "53") (name "Net-(RGB_LED-2)") (class "Default")
      (node (ref "R28") (pin "2") (pinfunction "2_2") (pintype "passive"))
      (node (ref "RGB_LED") (pin "P2") (pinfunction "2_P2") (pintype "bidirectional"))
    )
    (net (code "54") (name "Net-(RGB_LED-3)") (class "Default")
      (node (ref "R27") (pin "2") (pinfunction "2_2") (pintype "passive"))
      (node (ref "RGB_LED") (pin "P3") (pinfunction "3_P3") (pintype "bidirectional"))
    )
    (net (code "55") (name "Net-(RGB_LED-4)") (class "Default")
      (node (ref "R26") (pin "2") (pinfunction "2_2") (pintype "passive"))
      (node (ref "RGB_LED") (pin "P4") (pinfunction "4_P4") (pintype "bidirectional"))
    )
    (net (code "56") (name "Net-(STM32F103CB-OSC_OUT)") (class "Default")
      (node (ref "C36") (pin "2") (pinfunction "2_2") (pintype "passive"))
      (node (ref "KX-9A") (pin "1") (pinfunction "1_1") (pintype "passive"))
      (node (ref "STM32F103CB") (pin "6") (pinfunction "OSC_OUT_6") (pintype "bidirectional"))
    )
    (net (code "57") (name "Net-(STM32F103CB-PC13-TAMPER-RTC)") (class "Default")
      (node (ref "R30") (pin "1") (pinfunction "1_1") (pintype "passive"))
      (node (ref "STM32F103CB") (pin "2") (pinfunction "PC13-TAMPER-RTC_2") (pintype "bidirectional"))
    )
    (net (code "58") (name "V+") (class "Default")
      (node (ref "C16") (pin "1") (pinfunction "1_1") (pintype "passive"))
      (node (ref "C27") (pin "+") (pinfunction "+_+") (pintype "passive"))
      (node (ref "INA219") (pin "1") (pinfunction "VIN+_1") (pintype "bidirectional"))
      (node (ref "PWR") (pin "1") (pinfunction "1_1") (pintype "passive"))
      (node (ref "R17") (pin "2") (pinfunction "2_2") (pintype "passive"))
      (node (ref "R34") (pin "2") (pinfunction "2_2") (pintype "passive"))
    )
    (net (code "59") (name "unconnected-(MPU6050-AUX_CL-Pad7)") (class "Default")
      (node (ref "MPU6050") (pin "7") (pinfunction "AUX_CL_7") (pintype "input"))
    )
    (net (code "60") (name "unconnected-(MPU6050-AUX_DA-Pad6)") (class "Default")
      (node (ref "MPU6050") (pin "6") (pinfunction "AUX_DA_6") (pintype "bidirectional"))
    )
    (net (code "61") (name "unconnected-(MPU6050-RESV-Pad19)") (class "Default")
      (node (ref "MPU6050") (pin "19") (pinfunction "RESV_19") (pintype "passive"))
    )
    (net (code "62") (name "unconnected-(MPU6050-RESV-Pad21)") (class "Default")
      (node (ref "MPU6050") (pin "21") (pinfunction "RESV_21") (pintype "passive"))
    )
    (net (code "63") (name "unconnected-(MPU6050-RESV-Pad22)") (class "Default")
      (node (ref "MPU6050") (pin "22") (pinfunction "RESV_22") (pintype "passive"))
    )
    (net (code "64") (name "unconnected-(PCA9533-LED3-Pad5)") (class "Default")
      (node (ref "PCA9533") (pin "5") (pinfunction "LED3_5") (pintype "bidirectional"))
    )
    (net (code "65") (name "unconnected-(RPI_ZERO-Pad2)") (class "Default")
      (node (ref "RPI_ZERO") (pin "2") (pinfunction "2_2") (pintype "passive"))
    )
    (net (code "66") (name "unconnected-(RPI_ZERO-Pad3)") (class "Default")
      (node (ref "RPI_ZERO") (pin "3") (pinfunction "3_3") (pintype "passive"))
    )
    (net (code "67") (name "unconnected-(RPI_ZERO-Pad4)") (class "Default")
      (node (ref "RPI_ZERO") (pin "4") (pinfunction "4_4") (pintype "passive"))
    )
    (net (code "68") (name "unconnected-(RPI_ZERO-Pad5)") (class "Default")
      (node (ref "RPI_ZERO") (pin "5") (pinfunction "5_5") (pintype "passive"))
    )
    (net (code "69") (name "unconnected-(RPI_ZERO-Pad6)") (class "Default")
      (node (ref "RPI_ZERO") (pin "6") (pinfunction "6_6") (pintype "passive"))
    )
    (net (code "70") (name "unconnected-(RPI_ZERO-Pad7)") (class "Default")
      (node (ref "RPI_ZERO") (pin "7") (pinfunction "7_7") (pintype "passive"))
    )
    (net (code "71") (name "unconnected-(RPI_ZERO-Pad9)") (class "Default")
      (node (ref "RPI_ZERO") (pin "9") (pinfunction "9_9") (pintype "passive"))
    )
    (net (code "72") (name "unconnected-(RPI_ZERO-Pad10)") (class "Default")
      (node (ref "RPI_ZERO") (pin "10") (pinfunction "10_10") (pintype "passive"))
    )
    (net (code "73") (name "unconnected-(RPI_ZERO-Pad11)") (class "Default")
      (node (ref "RPI_ZERO") (pin "11") (pinfunction "11_11") (pintype "passive"))
    )
    (net (code "74") (name "unconnected-(RPI_ZERO-Pad13)") (class "Default")
      (node (ref "RPI_ZERO") (pin "13") (pinfunction "13_13") (pintype "passive"))
    )
    (net (code "75") (name "unconnected-(RPI_ZERO-Pad14)") (class "Default")
      (node (ref "RPI_ZERO") (pin "14") (pinfunction "14_14") (pintype "passive"))
    )
    (net (code "76") (name "unconnected-(RPI_ZERO-Pad16)") (class "Default")
      (node (ref "RPI_ZERO") (pin "16") (pinfunction "16_16") (pintype "passive"))
    )
    (net (code "77") (name "unconnected-(RPI_ZERO-Pad17)") (class "Default")
      (node (ref "RPI_ZERO") (pin "17") (pinfunction "17_17") (pintype "passive"))
    )
    (net (code "78") (name "unconnected-(RPI_ZERO-Pad18)") (class "Default")
      (node (ref "RPI_ZERO") (pin "18") (pinfunction "18_18") (pintype "passive"))
    )
    (net (code "79") (name "unconnected-(RPI_ZERO-Pad19)") (class "Default")
      (node (ref "RPI_ZERO") (pin "19") (pinfunction "19_19") (pintype "passive"))
    )
    (net (code "80") (name "unconnected-(RPI_ZERO-Pad21)") (class "Default")
      (node (ref "RPI_ZERO") (pin "21") (pinfunction "21_21") (pintype "passive"))
    )
    (net (code "81") (name "unconnected-(RPI_ZERO-Pad23)") (class "Default")
      (node (ref "RPI_ZERO") (pin "23") (pinfunction "23_23") (pintype "passive"))
    )
    (net (code "82") (name "unconnected-(RPI_ZERO-Pad25)") (class "Default")
      (node (ref "RPI_ZERO") (pin "25") (pinfunction "25_25") (pintype "passive"))
    )
    (net (code "83") (name "unconnected-(RPI_ZERO-Pad27)") (class "Default")
      (node (ref "RPI_ZERO") (pin "27") (pinfunction "27_27") (pintype "passive"))
    )
    (net (code "84") (name "unconnected-(RPI_ZERO-Pad29)") (class "Default")
      (node (ref "RPI_ZERO") (pin "29") (pinfunction "29_29") (pintype "passive"))
    )
    (net (code "85") (name "unconnected-(RPI_ZERO-Pad30)") (class "Default")
      (node (ref "RPI_ZERO") (pin "30") (pinfunction "30_30") (pintype "passive"))
    )
    (net (code "86") (name "unconnected-(RPI_ZERO-Pad33)") (class "Default")
      (node (ref "RPI_ZERO") (pin "33") (pinfunction "33_33") (pintype "passive"))
    )
    (net (code "87") (name "unconnected-(RPI_ZERO-Pad35)") (class "Default")
      (node (ref "RPI_ZERO") (pin "35") (pinfunction "35_35") (pintype "passive"))
    )
    (net (code "88") (name "unconnected-(RPI_ZERO-Pad37)") (class "Default")
      (node (ref "RPI_ZERO") (pin "37") (pinfunction "37_37") (pintype "passive"))
    )
    (net (code "89") (name "unconnected-(RPI_ZERO-Pad39)") (class "Default")
      (node (ref "RPI_ZERO") (pin "39") (pinfunction "39_39") (pintype "passive"))
    )
    (net (code "90") (name "unconnected-(STM32F103CB-PA1-Pad11)") (class "Default")
      (node (ref "STM32F103CB") (pin "11") (pinfunction "PA1_11") (pintype "bidirectional"))
    )
    (net (code "91") (name "unconnected-(STM32F103CB-PA8-Pad29)") (class "Default")
      (node (ref "STM32F103CB") (pin "29") (pinfunction "PA8_29") (pintype "bidirectional"))
    )
    (net (code "92") (name "unconnected-(STM32F103CB-PB4-Pad40)") (class "Default")
      (node (ref "STM32F103CB") (pin "40") (pinfunction "PB4_40") (pintype "bidirectional"))
    )
    (net (code "93") (name "unconnected-(STM32F103CB-PB5-Pad41)") (class "Default")
      (node (ref "STM32F103CB") (pin "41") (pinfunction "PB5_41") (pintype "bidirectional"))
    )
    (net (code "94") (name "unconnected-(STM32F103CB-PB8-Pad45)") (class "Default")
      (node (ref "STM32F103CB") (pin "45") (pinfunction "PB8_45") (pintype "bidirectional"))
    )
    (net (code "95") (name "unconnected-(STM32F103CB-PB9-Pad46)") (class "Default")
      (node (ref "STM32F103CB") (pin "46") (pinfunction "PB9_46") (pintype "bidirectional"))
    )
    (net (code "96") (name "unconnected-(STM32F103CB-PB10-Pad21)") (class "Default")
      (node (ref "STM32F103CB") (pin "21") (pinfunction "PB10_21") (pintype "bidirectional"))
    )
    (net (code "97") (name "unconnected-(STM32F103CB-PB11-Pad22)") (class "Default")
      (node (ref "STM32F103CB") (pin "22") (pinfunction "PB11_22") (pintype "bidirectional"))
    )
    (net (code "98") (name "unconnected-(STM32F103CB-PB13-Pad26)") (class "Default")
      (node (ref "STM32F103CB") (pin "26") (pinfunction "PB13_26") (pintype "bidirectional"))
    )
    (net (code "99") (name "unconnected-(STM32F103CB-PC14-OSC32_IN-Pad3)") (class "Default")
      (node (ref "STM32F103CB") (pin "3") (pinfunction "PC14-OSC32_IN_3") (pintype "bidirectional"))
    )
    (net (code "100") (name "unconnected-(STM32F103CB-PC15-OSC32_OUT-Pad4)") (class "Default")
      (node (ref "STM32F103CB") (pin "4") (pinfunction "PC15-OSC32_OUT_4") (pintype "bidirectional"))
    )
  )
)
